# easyeda_prj.net
KiCad netlist of a schematic drawn in EasyEDA
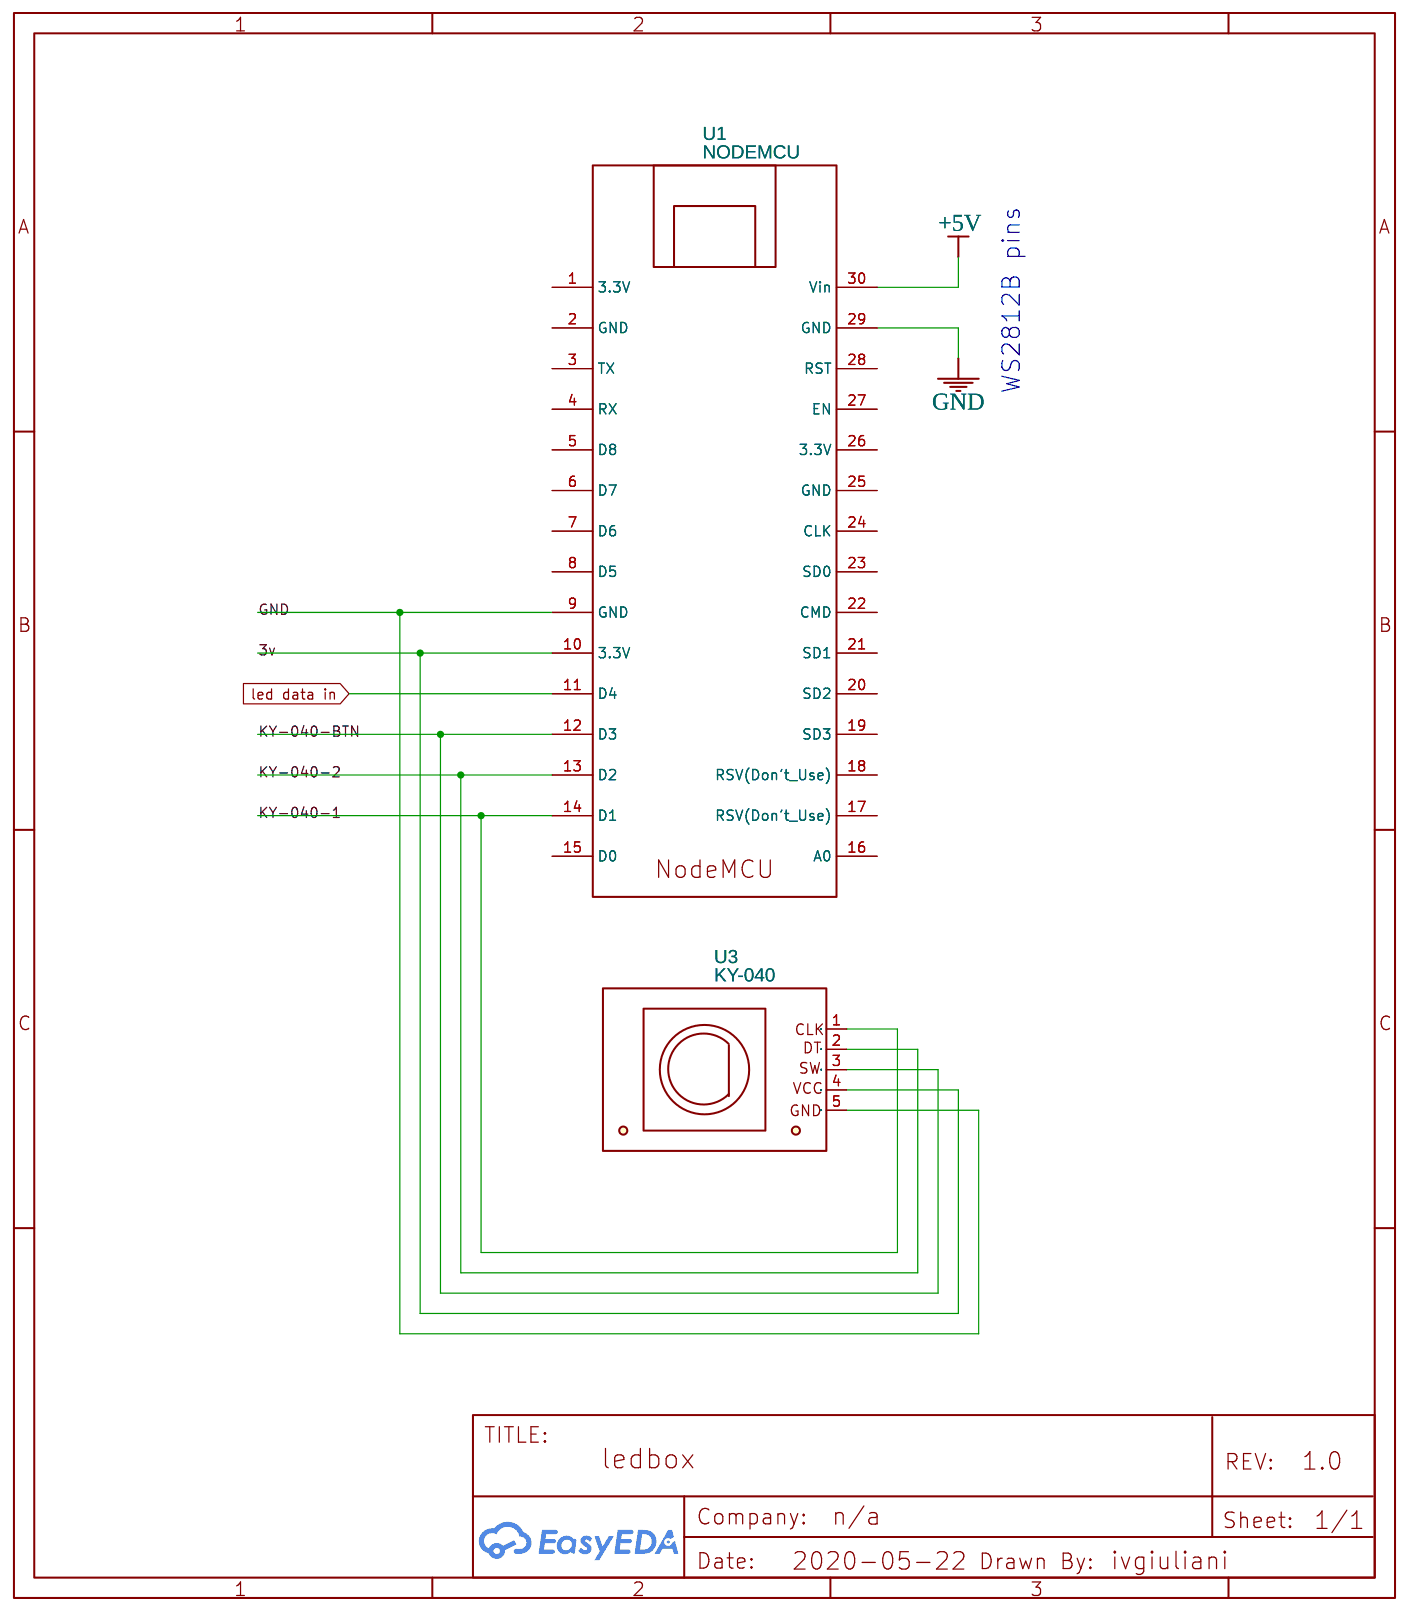
[diagram p0: schematic sheet]

(export (version "E")
  (design (tool "Eeschema 10.0.6"))
  (components
    (comp (ref "U1") (value "NODEMCU") (libsource (lib "") (part "NODEMCU")))
    (comp (ref "U3") (value "KY-040") (libsource (lib "") (part "KY-040")))
  )
  (nets
    (net (code "1") (name "+5V") (class "Default")
      (node (ref "U1") (pin "30") (pinfunction "Vin_30") (pintype "unspecified"))
    )
    (net (code "2") (name "/3v") (class "Default")
      (node (ref "U1") (pin "10") (pinfunction "3.3V_10") (pintype "unspecified"))
      (node (ref "U3") (pin "4") (pinfunction "VCC_4") (pintype "unspecified"))
    )
    (net (code "3") (name "/KY-040-1") (class "Default")
      (node (ref "U1") (pin "14") (pinfunction "D1_14") (pintype "unspecified"))
      (node (ref "U3") (pin "1") (pinfunction "CLK_1") (pintype "unspecified"))
    )
    (net (code "4") (name "/KY-040-2") (class "Default")
      (node (ref "U1") (pin "13") (pinfunction "D2_13") (pintype "unspecified"))
      (node (ref "U3") (pin "2") (pinfunction "DT_2") (pintype "unspecified"))
    )
    (net (code "5") (name "/KY-040-BTN") (class "Default")
      (node (ref "U1") (pin "12") (pinfunction "D3_12") (pintype "unspecified"))
      (node (ref "U3") (pin "3") (pinfunction "SW_3") (pintype "unspecified"))
    )
    (net (code "6") (name "GND") (class "Default")
      (node (ref "U1") (pin "29") (pinfunction "GND_29") (pintype "unspecified"))
      (node (ref "U1") (pin "9") (pinfunction "GND_9") (pintype "unspecified"))
      (node (ref "U3") (pin "5") (pinfunction "GND_5") (pintype "unspecified"))
    )
    (net (code "7") (name "led data in") (class "Default")
      (node (ref "U1") (pin "11") (pinfunction "D4_11") (pintype "unspecified"))
    )
    (net (code "8") (name "unconnected-(U1-3.3V-Pad1)") (class "Default")
      (node (ref "U1") (pin "1") (pinfunction "3.3V_1") (pintype "unspecified"))
    )
    (net (code "9") (name "unconnected-(U1-3.3V-Pad26)") (class "Default")
      (node (ref "U1") (pin "26") (pinfunction "3.3V_26") (pintype "unspecified"))
    )
    (net (code "10") (name "unconnected-(U1-A0-Pad16)") (class "Default")
      (node (ref "U1") (pin "16") (pinfunction "A0_16") (pintype "unspecified"))
    )
    (net (code "11") (name "unconnected-(U1-CLK-Pad24)") (class "Default")
      (node (ref "U1") (pin "24") (pinfunction "CLK_24") (pintype "unspecified"))
    )
    (net (code "12") (name "unconnected-(U1-CMD-Pad22)") (class "Default")
      (node (ref "U1") (pin "22") (pinfunction "CMD_22") (pintype "unspecified"))
    )
    (net (code "13") (name "unconnected-(U1-D0-Pad15)") (class "Default")
      (node (ref "U1") (pin "15") (pinfunction "D0_15") (pintype "unspecified"))
    )
    (net (code "14") (name "unconnected-(U1-D5-Pad8)") (class "Default")
      (node (ref "U1") (pin "8") (pinfunction "D5_8") (pintype "unspecified"))
    )
    (net (code "15") (name "unconnected-(U1-D6-Pad7)") (class "Default")
      (node (ref "U1") (pin "7") (pinfunction "D6_7") (pintype "unspecified"))
    )
    (net (code "16") (name "unconnected-(U1-D7-Pad6)") (class "Default")
      (node (ref "U1") (pin "6") (pinfunction "D7_6") (pintype "unspecified"))
    )
    (net (code "17") (name "unconnected-(U1-D8-Pad5)") (class "Default")
      (node (ref "U1") (pin "5") (pinfunction "D8_5") (pintype "unspecified"))
    )
    (net (code "18") (name "unconnected-(U1-EN-Pad27)") (class "Default")
      (node (ref "U1") (pin "27") (pinfunction "EN_27") (pintype "unspecified"))
    )
    (net (code "19") (name "unconnected-(U1-GND-Pad2)") (class "Default")
      (node (ref "U1") (pin "2") (pinfunction "GND_2") (pintype "unspecified"))
    )
    (net (code "20") (name "unconnected-(U1-GND-Pad25)") (class "Default")
      (node (ref "U1") (pin "25") (pinfunction "GND_25") (pintype "unspecified"))
    )
    (net (code "21") (name "unconnected-(U1-RST-Pad28)") (class "Default")
      (node (ref "U1") (pin "28") (pinfunction "RST_28") (pintype "unspecified"))
    )
    (net (code "22") (name "unconnected-(U1-RSV(Don't_Use)-Pad17)") (class "Default")
      (node (ref "U1") (pin "17") (pinfunction "RSV(Don't_Use)_17") (pintype "unspecified"))
    )
    (net (code "23") (name "unconnected-(U1-RSV(Don't_Use)-Pad18)") (class "Default")
      (node (ref "U1") (pin "18") (pinfunction "RSV(Don't_Use)_18") (pintype "unspecified"))
    )
    (net (code "24") (name "unconnected-(U1-RX-Pad4)") (class "Default")
      (node (ref "U1") (pin "4") (pinfunction "RX_4") (pintype "unspecified"))
    )
    (net (code "25") (name "unconnected-(U1-SD0-Pad23)") (class "Default")
      (node (ref "U1") (pin "23") (pinfunction "SD0_23") (pintype "unspecified"))
    )
    (net (code "26") (name "unconnected-(U1-SD1-Pad21)") (class "Default")
      (node (ref "U1") (pin "21") (pinfunction "SD1_21") (pintype "unspecified"))
    )
    (net (code "27") (name "unconnected-(U1-SD2-Pad20)") (class "Default")
      (node (ref "U1") (pin "20") (pinfunction "SD2_20") (pintype "unspecified"))
    )
    (net (code "28") (name "unconnected-(U1-SD3-Pad19)") (class "Default")
      (node (ref "U1") (pin "19") (pinfunction "SD3_19") (pintype "unspecified"))
    )
    (net (code "29") (name "unconnected-(U1-TX-Pad3)") (class "Default")
      (node (ref "U1") (pin "3") (pinfunction "TX_3") (pintype "unspecified"))
    )
  )
)
